# Servo_control_module.net
KiCad netlist of a schematic drawn in Altium Designer
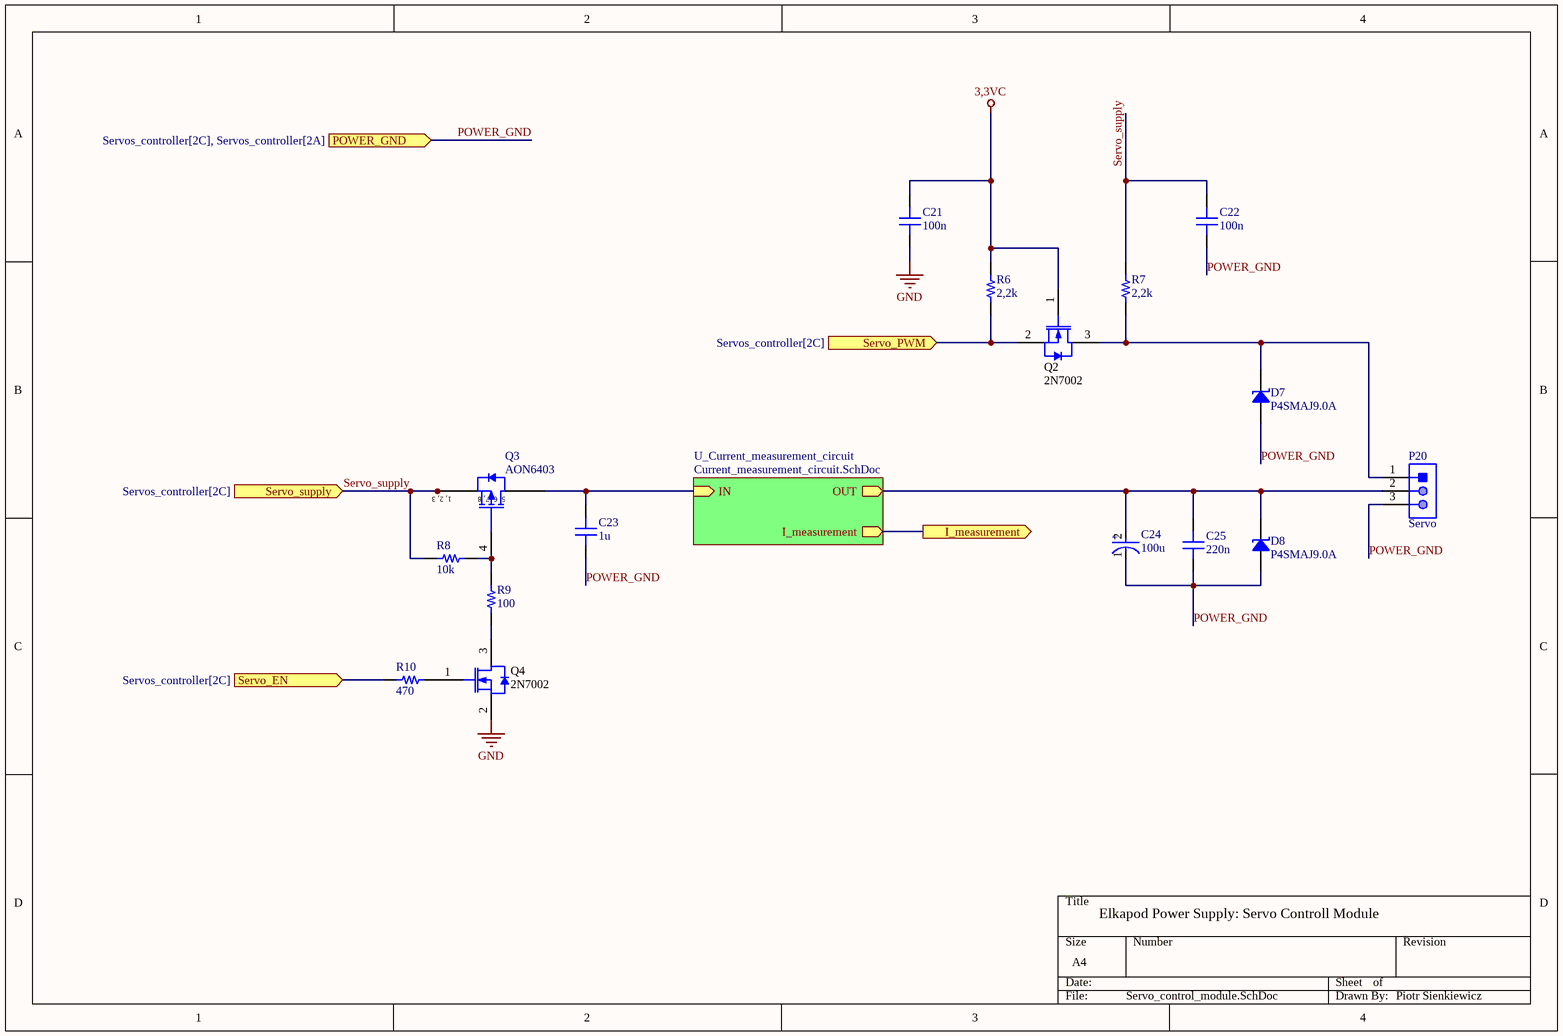
[diagram p0: Servo_control_module.SchDoc]

(export (version "E")
  (design (tool "Eeschema 10.0.6"))
  (components
    (comp (ref "C21")
      (value "100n")
      (footprint "CAP 0603_1608")
      (description "CAP CER 100nF 25V X5R 0603")
      (fields (field (name "PART NUMBER") "C0603C272F3GAC7867") (field (name "MANUFACTURER") "KEMET"))
      (libsource (lib "Celestial Altium Library - altium_library") (part "Capacitor"))
    )
    (comp (ref "C22")
      (value "100n")
      (footprint "CAP 0603_1608")
      (description "CAP CER 100nF 25V X5R 0603")
      (fields (field (name "PART NUMBER") "C0603C272F3GAC7867") (field (name "MANUFACTURER") "KEMET"))
      (libsource (lib "Celestial Altium Library - altium_library") (part "Capacitor"))
    )
    (comp (ref "C23")
      (value "1u")
      (footprint "CAP 0603_1608")
      (description "CAP CER 1uF 16V X5R 0603")
      (fields (field (name "PART NUMBER") "C0603C272F3GAC7867") (field (name "MANUFACTURER") "KEMET"))
      (libsource (lib "Celestial Altium Library - altium_library") (part "Capacitor"))
    )
    (comp (ref "C24")
      (value "100u")
      (footprint "FP-FKE-MFG")
      (description "CAP ALUM 100UF 20% 25V SMD")
      (fields (field (name "TOLERANCE") "20%") (field (name "VOLTAGE") "25V"))
      (libsource (lib "Altium Content Vault") (part "203bc49f2ac43e59fd269a8c329ed05"))
    )
    (comp (ref "C25")
      (value "220n")
      (footprint "CAP 0603_1608")
      (description "CAP CER 220nF 25V X5R 0603")
      (fields (field (name "PART NUMBER") "C0603C272F3GAC7867") (field (name "MANUFACTURER") "KEMET"))
      (libsource (lib "Celestial Altium Library - altium_library") (part "Capacitor"))
    )
    (comp (ref "D7")
      (value "P4SMAJ9.0A")
      (footprint "DO214AC SMA")
      (description "TVS DIODE 9VDC DO214AC")
      (libsource (lib "Celestial Altium Library - altium_library") (part "DIODE TVS UNI"))
    )
    (comp (ref "D8")
      (value "P4SMAJ9.0A")
      (footprint "DO214AC SMA")
      (description "TVS DIODE 9VDC DO214AC")
      (libsource (lib "Celestial Altium Library - altium_library") (part "DIODE TVS UNI"))
    )
    (comp (ref "P20")
      (value "Servo")
      (footprint "MOLX-22-23-2031_V")
      (description "Male Header, Pitch 2.54 mm, 1 x 3 Position, Height 8.18 mm, Tail Length 3.56 mm, RoHS, Bulk")
      (fields (field (name "MANUFACTURER") "Molex"))
      (libsource (lib "Altium Content Vault") (part "CN-1P-M-R3"))
    )
    (comp (ref "Q2")
      (value "2N7002")
      (footprint "INF-PG-SOT23_M")
      (fields (field (name "MANUFACTURER") "Infineon"))
      (libsource (lib "Altium Content Vault") (part "INF-NDMOS-GSD-3"))
    )
    (comp (ref "Q3")
      (value "AON6403")
      (footprint "DFN5x6")
      (description "P-MOSFET; 67A; 30V; DFN5x6")
      (libsource (lib "My_transistors") (part "AON6403"))
    )
    (comp (ref "Q4")
      (value "2N7002")
      (footprint "INF-PG-SOT23_M")
      (fields (field (name "MANUFACTURER") "Infineon"))
      (libsource (lib "Altium Content Vault") (part "INF-NDMOS-GSD-3"))
    )
    (comp (ref "R6")
      (value "2,2k")
      (footprint "RES 0603_1608")
      (description "RES 2,2K OHM 1% 0,1W 0603")
      (fields
        (field (name "PART NUMBER") "RNCS0603BKE10K0")
        (field (name "MANUFACTURER") "Stackpole Electronics Inc")
      )
      (libsource (lib "Celestial Altium Library - altium_library") (part "Resistor"))
    )
    (comp (ref "R7")
      (value "2,2k")
      (footprint "RES 0603_1608")
      (description "RES 2,2K OHM 1% 0,1W 0603")
      (fields
        (field (name "PART NUMBER") "RNCS0603BKE10K0")
        (field (name "MANUFACTURER") "Stackpole Electronics Inc")
      )
      (libsource (lib "Celestial Altium Library - altium_library") (part "Resistor"))
    )
    (comp (ref "R8")
      (value "10k")
      (footprint "RES 0603_1608")
      (description "RES 10K OHM 1% 0,1W 0603")
      (fields
        (field (name "PART NUMBER") "RNCS0603BKE10K0")
        (field (name "MANUFACTURER") "Stackpole Electronics Inc")
      )
      (libsource (lib "Celestial Altium Library - altium_library") (part "Resistor"))
    )
    (comp (ref "R9")
      (value "100")
      (footprint "RES 0603_1608")
      (description "RES 100 OHM 1% 0,1W 0603")
      (fields
        (field (name "PART NUMBER") "RNCS0603BKE10K0")
        (field (name "MANUFACTURER") "Stackpole Electronics Inc")
      )
      (libsource (lib "Celestial Altium Library - altium_library") (part "Resistor"))
    )
    (comp (ref "R10")
      (value "470")
      (footprint "RES 0603_1608")
      (description "RES 470 OHM 1% 0,1W 0603")
      (fields
        (field (name "PART NUMBER") "RNCS0603BKE10K0")
        (field (name "MANUFACTURER") "Stackpole Electronics Inc")
      )
      (libsource (lib "Celestial Altium Library - altium_library") (part "Resistor"))
    )
  )
  (nets
    (net (code "1") (name "/IN") (class "Default")
      (node (ref "C23") (pin "2") (pinfunction "2_2") (pintype "passive"))
      (node (ref "Q3") (pin "5") (pinfunction "D_5") (pintype "passive"))
    )
    (net (code "3") (name "/OUT") (class "Default")
      (node (ref "C24") (pin "2") (pinfunction "A_2") (pintype "passive"))
      (node (ref "C25") (pin "1") (pinfunction "1_1") (pintype "passive"))
      (node (ref "D8") (pin "2") (pinfunction "2_2") (pintype "passive"))
      (node (ref "P20") (pin "2") (pinfunction "2_2") (pintype "passive"))
    )
    (net (code "4") (name "/POWER_GND") (class "Default")
      (node (ref "C22") (pin "1") (pinfunction "1_1") (pintype "passive"))
      (node (ref "C23") (pin "1") (pinfunction "1_1") (pintype "passive"))
      (node (ref "C24") (pin "1") (pinfunction "C_1") (pintype "passive"))
      (node (ref "C25") (pin "2") (pinfunction "2_2") (pintype "passive"))
      (node (ref "D7") (pin "1") (pinfunction "1_1") (pintype "passive"))
      (node (ref "D8") (pin "1") (pinfunction "1_1") (pintype "passive"))
      (node (ref "P20") (pin "3") (pinfunction "3_3") (pintype "passive"))
    )
    (net (code "5") (name "/Servo_EN") (class "Default")
      (node (ref "R10") (pin "1") (pinfunction "1_1") (pintype "passive"))
    )
    (net (code "6") (name "/Servo_PWM") (class "Default")
      (node (ref "Q2") (pin "2") (pinfunction "SOURCE_2") (pintype "passive"))
      (node (ref "R6") (pin "1") (pinfunction "1_1") (pintype "passive"))
    )
    (net (code "7") (name "/Servo_supply") (class "Default")
      (node (ref "C22") (pin "2") (pinfunction "2_2") (pintype "passive"))
      (node (ref "Q3") (pin "1") (pinfunction "S_1") (pintype "passive"))
      (node (ref "Q3") (pin "2") (pinfunction "S_2") (pintype "passive"))
      (node (ref "Q3") (pin "3") (pinfunction "S_3") (pintype "passive"))
      (node (ref "R7") (pin "2") (pinfunction "2_2") (pintype "passive"))
      (node (ref "R8") (pin "1") (pinfunction "1_1") (pintype "passive"))
    )
    (net (code "8") (name "3,3VC") (class "Default")
      (node (ref "C21") (pin "2") (pinfunction "2_2") (pintype "passive"))
      (node (ref "Q2") (pin "1") (pinfunction "GATE_1") (pintype "passive"))
      (node (ref "R6") (pin "2") (pinfunction "2_2") (pintype "passive"))
    )
    (net (code "9") (name "GND") (class "Default")
      (node (ref "C21") (pin "1") (pinfunction "1_1") (pintype "passive"))
      (node (ref "Q4") (pin "2") (pinfunction "SOURCE_2") (pintype "passive"))
    )
    (net (code "10") (name "Net-(Q2-DRAIN)") (class "Default")
      (node (ref "D7") (pin "2") (pinfunction "2_2") (pintype "passive"))
      (node (ref "P20") (pin "1") (pinfunction "1_1") (pintype "passive"))
      (node (ref "Q2") (pin "3") (pinfunction "DRAIN_3") (pintype "passive"))
      (node (ref "R7") (pin "1") (pinfunction "1_1") (pintype "passive"))
    )
    (net (code "11") (name "Net-(Q3-G)") (class "Default")
      (node (ref "Q3") (pin "4") (pinfunction "G_4") (pintype "passive"))
      (node (ref "R8") (pin "2") (pinfunction "2_2") (pintype "passive"))
      (node (ref "R9") (pin "2") (pinfunction "2_2") (pintype "passive"))
    )
    (net (code "12") (name "Net-(Q4-DRAIN)") (class "Default")
      (node (ref "Q4") (pin "3") (pinfunction "DRAIN_3") (pintype "passive"))
      (node (ref "R9") (pin "1") (pinfunction "1_1") (pintype "passive"))
    )
    (net (code "13") (name "Net-(Q4-GATE)") (class "Default")
      (node (ref "Q4") (pin "1") (pinfunction "GATE_1") (pintype "passive"))
      (node (ref "R10") (pin "2") (pinfunction "2_2") (pintype "passive"))
    )
  )
)
